# 1-Schematic_Cowboy-key.net
KiCad netlist of a schematic drawn in EasyEDA
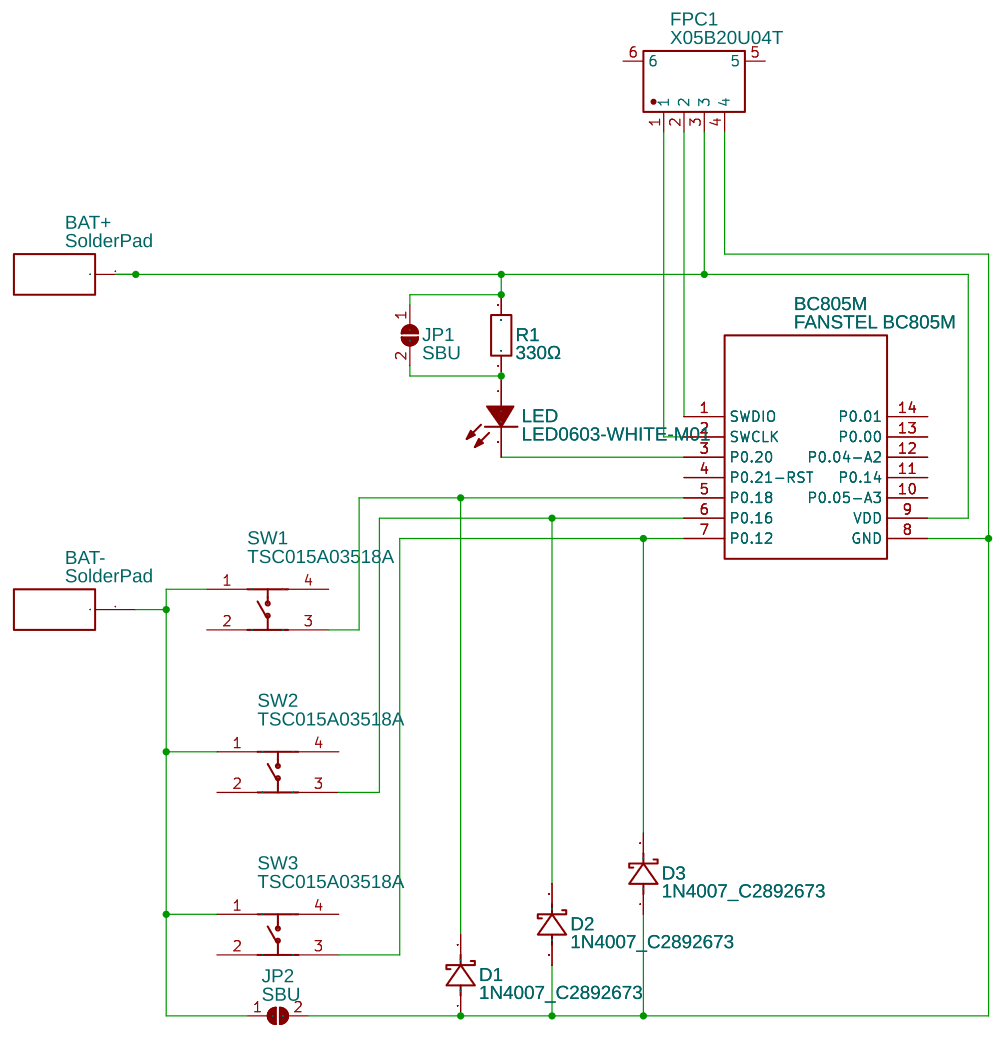
[diagram p0: schematic sheet]

(export (version "E")
  (design (tool "Eeschema 10.0.6"))
  (components
    (comp (ref "BAT+") (value "SolderPad") (libsource (lib "") (part "SolderPad")))
    (comp (ref "BAT-") (value "SolderPad") (libsource (lib "") (part "SolderPad_1")))
    (comp (ref "BC805M")
      (value "FANSTEL BC805M")
      (fields (field (name "BOM_Manufacturer Part") "BC805M"))
      (libsource (lib "") (part "FANSTEL BC805M"))
    )
    (comp (ref "D1")
      (value "1N4007_C2892673")
      (fields (field (name "BOM_Manufacturer Part") "1N4007") (field (name "BOM_Supplier Part") "C2892673"))
      (libsource (lib "") (part "1N4007_C2892673"))
    )
    (comp (ref "D2")
      (value "1N4007_C2892673")
      (fields (field (name "BOM_Manufacturer Part") "1N4007") (field (name "BOM_Supplier Part") "C2892673"))
      (libsource (lib "") (part "1N4007_C2892673"))
    )
    (comp (ref "D3")
      (value "1N4007_C2892673")
      (fields (field (name "BOM_Manufacturer Part") "1N4007") (field (name "BOM_Supplier Part") "C2892673"))
      (libsource (lib "") (part "1N4007_C2892673"))
    )
    (comp (ref "FPC1")
      (value "X05B20U04T")
      (fields (field (name "BOM_Supplier Part") "C388690"))
      (libsource (lib "") (part "X05B20U04T"))
    )
    (comp (ref "JP1")
      (value "SBU")
      (fields (field (name "BOM_Manufacturer Part") "DNP"))
      (libsource (lib "") (part "SBU"))
    )
    (comp (ref "JP2")
      (value "SBU")
      (fields (field (name "BOM_Manufacturer Part") "DNP"))
      (libsource (lib "") (part "SBU_1"))
    )
    (comp (ref "LED")
      (value "LED0603-WHITE-M01")
      (fields
        (field (name "BOM_Manufacturer Part") "LTW-C191TS5")
        (field (name "BOM_Supplier Part") "C125123")
      )
      (libsource (lib "") (part "LED0603-WHITE-M01"))
    )
    (comp (ref "R1")
      (value "330Ω")
      (fields
        (field (name "BOM_Manufacturer Part") "SCR0603F330R")
        (field (name "BOM_Supplier Part") "C3016255")
      )
      (libsource (lib "") (part "SCR0603F330R"))
    )
    (comp (ref "SW1")
      (value "TSC015A03518A")
      (fields (field (name "BOM_Supplier Part") "C2888502"))
      (libsource (lib "") (part "TSC015A03518A"))
    )
    (comp (ref "SW2")
      (value "TSC015A03518A")
      (fields (field (name "BOM_Supplier Part") "C2888502"))
      (libsource (lib "") (part "TSC015A03518A"))
    )
    (comp (ref "SW3")
      (value "TSC015A03518A")
      (fields (field (name "BOM_Supplier Part") "C2888502"))
      (libsource (lib "") (part "TSC015A03518A"))
    )
  )
  (nets
    (net (code "1") (name "Net-(BC805M-GND)") (class "Default")
      (node (ref "BC805M") (pin "8") (pinfunction "GND_8") (pintype "unspecified"))
      (node (ref "D1") (pin "1") (pinfunction "A_1") (pintype "unspecified"))
      (node (ref "D2") (pin "1") (pinfunction "A_1") (pintype "unspecified"))
      (node (ref "D3") (pin "1") (pinfunction "A_1") (pintype "unspecified"))
      (node (ref "FPC1") (pin "4") (pinfunction "4_4") (pintype "unspecified"))
      (node (ref "JP2") (pin "2") (pinfunction "B_2") (pintype "unspecified"))
    )
    (net (code "2") (name "Net-(BC805M-P0.12)") (class "Default")
      (node (ref "BC805M") (pin "7") (pinfunction "P0.12_7") (pintype "unspecified"))
      (node (ref "D3") (pin "2") (pinfunction "K_2") (pintype "unspecified"))
      (node (ref "SW3") (pin "3") (pinfunction "3_3") (pintype "unspecified"))
    )
    (net (code "3") (name "Net-(BC805M-P0.16)") (class "Default")
      (node (ref "BC805M") (pin "6") (pinfunction "P0.16_6") (pintype "unspecified"))
      (node (ref "D2") (pin "2") (pinfunction "K_2") (pintype "unspecified"))
      (node (ref "SW2") (pin "3") (pinfunction "3_3") (pintype "unspecified"))
    )
    (net (code "4") (name "Net-(BC805M-P0.18)") (class "Default")
      (node (ref "BC805M") (pin "5") (pinfunction "P0.18_5") (pintype "unspecified"))
      (node (ref "D1") (pin "2") (pinfunction "K_2") (pintype "unspecified"))
      (node (ref "SW1") (pin "3") (pinfunction "3_3") (pintype "unspecified"))
    )
    (net (code "5") (name "Net-(BC805M-P0.20)") (class "Default")
      (node (ref "BC805M") (pin "3") (pinfunction "P0.20_3") (pintype "unspecified"))
      (node (ref "LED") (pin "2") (pinfunction "K_2") (pintype "unspecified"))
    )
    (net (code "6") (name "Net-(BC805M-SWCLK)") (class "Default")
      (node (ref "BC805M") (pin "2") (pinfunction "SWCLK_2") (pintype "unspecified"))
      (node (ref "FPC1") (pin "1") (pinfunction "1_1") (pintype "unspecified"))
    )
    (net (code "7") (name "Net-(BC805M-SWDIO)") (class "Default")
      (node (ref "BC805M") (pin "1") (pinfunction "SWDIO_1") (pintype "unspecified"))
      (node (ref "FPC1") (pin "2") (pinfunction "2_2") (pintype "unspecified"))
    )
    (net (code "8") (name "Net-(BC805M-VDD)") (class "Default")
      (node (ref "BAT+") (pin "1") (pinfunction "1_1") (pintype "unspecified"))
      (node (ref "BC805M") (pin "9") (pinfunction "VDD_9") (pintype "unspecified"))
      (node (ref "FPC1") (pin "3") (pinfunction "3_3") (pintype "unspecified"))
      (node (ref "JP1") (pin "1") (pinfunction "A_1") (pintype "unspecified"))
      (node (ref "R1") (pin "2") (pinfunction "2_2") (pintype "unspecified"))
    )
    (net (code "9") (name "Net-(JP1-B)") (class "Default")
      (node (ref "JP1") (pin "2") (pinfunction "B_2") (pintype "unspecified"))
      (node (ref "LED") (pin "1") (pinfunction "A_1") (pintype "unspecified"))
      (node (ref "R1") (pin "1") (pinfunction "1_1") (pintype "unspecified"))
    )
    (net (code "10") (name "Net-(JP2-A)") (class "Default")
      (node (ref "BAT-") (pin "1") (pinfunction "1_1") (pintype "unspecified"))
      (node (ref "JP2") (pin "1") (pinfunction "A_1") (pintype "unspecified"))
      (node (ref "SW1") (pin "1") (pinfunction "1_1") (pintype "unspecified"))
      (node (ref "SW2") (pin "1") (pinfunction "1_1") (pintype "unspecified"))
      (node (ref "SW3") (pin "1") (pinfunction "1_1") (pintype "unspecified"))
    )
    (net (code "11") (name "unconnected-(BC805M-P0.00-Pad13)") (class "Default")
      (node (ref "BC805M") (pin "13") (pinfunction "P0.00_13") (pintype "unspecified"))
    )
    (net (code "12") (name "unconnected-(BC805M-P0.01-Pad14)") (class "Default")
      (node (ref "BC805M") (pin "14") (pinfunction "P0.01_14") (pintype "unspecified"))
    )
    (net (code "13") (name "unconnected-(BC805M-P0.04-A2-Pad12)") (class "Default")
      (node (ref "BC805M") (pin "12") (pinfunction "P0.04-A2_12") (pintype "unspecified"))
    )
    (net (code "14") (name "unconnected-(BC805M-P0.05-A3-Pad10)") (class "Default")
      (node (ref "BC805M") (pin "10") (pinfunction "P0.05-A3_10") (pintype "unspecified"))
    )
    (net (code "15") (name "unconnected-(BC805M-P0.14-Pad11)") (class "Default")
      (node (ref "BC805M") (pin "11") (pinfunction "P0.14_11") (pintype "unspecified"))
    )
    (net (code "16") (name "unconnected-(BC805M-P0.21-RST-Pad4)") (class "Default")
      (node (ref "BC805M") (pin "4") (pinfunction "P0.21-RST_4") (pintype "unspecified"))
    )
    (net (code "17") (name "unconnected-(FPC1-Pad5)") (class "Default")
      (node (ref "FPC1") (pin "5") (pinfunction "5_5") (pintype "unspecified"))
    )
    (net (code "18") (name "unconnected-(FPC1-Pad6)") (class "Default")
      (node (ref "FPC1") (pin "6") (pinfunction "6_6") (pintype "unspecified"))
    )
    (net (code "19") (name "unconnected-(SW1-Pad2)") (class "Default")
      (node (ref "SW1") (pin "2") (pinfunction "2_2") (pintype "unspecified"))
    )
    (net (code "20") (name "unconnected-(SW1-Pad4)") (class "Default")
      (node (ref "SW1") (pin "4") (pinfunction "4_4") (pintype "unspecified"))
    )
    (net (code "21") (name "unconnected-(SW2-Pad2)") (class "Default")
      (node (ref "SW2") (pin "2") (pinfunction "2_2") (pintype "unspecified"))
    )
    (net (code "22") (name "unconnected-(SW2-Pad4)") (class "Default")
      (node (ref "SW2") (pin "4") (pinfunction "4_4") (pintype "unspecified"))
    )
    (net (code "23") (name "unconnected-(SW3-Pad2)") (class "Default")
      (node (ref "SW3") (pin "2") (pinfunction "2_2") (pintype "unspecified"))
    )
    (net (code "24") (name "unconnected-(SW3-Pad4)") (class "Default")
      (node (ref "SW3") (pin "4") (pinfunction "4_4") (pintype "unspecified"))
    )
  )
)
